# nRF24L01-Module.net
KiCad netlist of a schematic drawn in Altium Designer
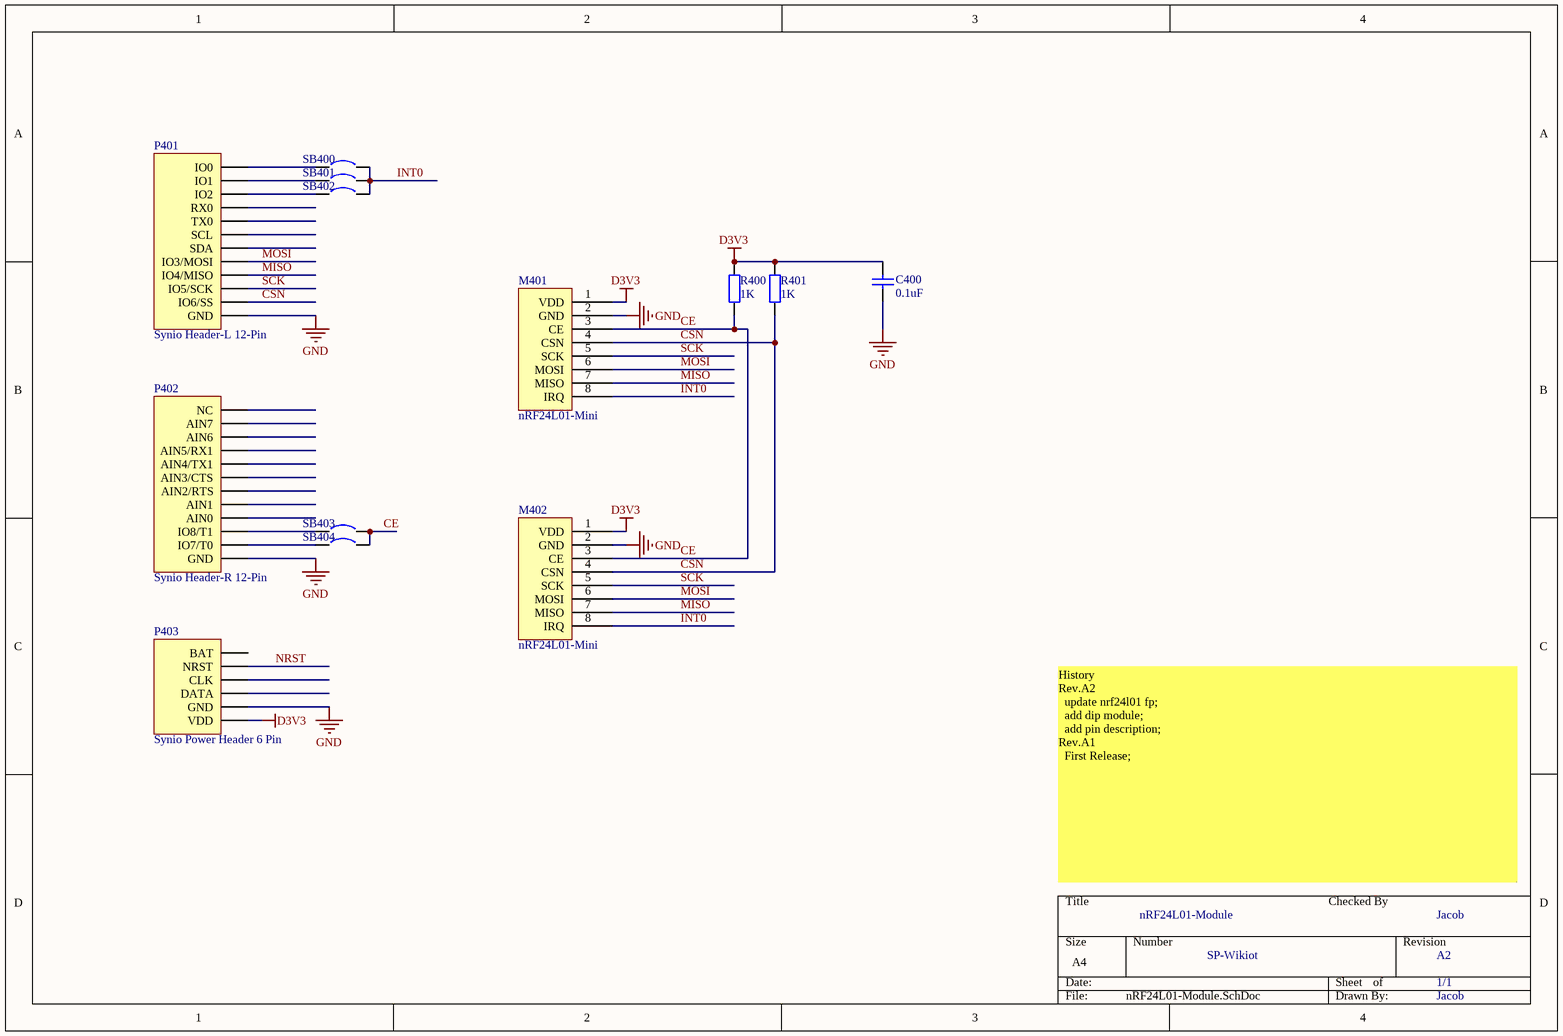
[diagram p0: nRF24L01-Module.SchDoc]

(export (version "E")
  (design (tool "Eeschema 10.0.6"))
  (components
    (comp (ref "C400")
      (value "0.1uF")
      (footprint "C0603L")
      (description "Capacitor")
      (libsource (lib "Misc") (part "Cap"))
    )
    (comp (ref "M401")
      (value "nRF24L01-Mini")
      (footprint "nRF24L01-Mini-All")
      (libsource (lib "Module") (part "nRF24L01-Mini"))
    )
    (comp (ref "M402")
      (value "nRF24L01-Mini")
      (footprint "nRF24L01-DIP")
      (libsource (lib "Module") (part "nRF24L01-Mini"))
    )
    (comp (ref "P401")
      (value "Synio Header-L 12-Pin")
      (footprint "HDR1X12")
      (description "Synio Header-L, 12-Pin")
      (fields (field (name "PUBLISHER") "Altium Limited"))
      (libsource (lib "Connector") (part "Synio Header-L 12-Pin"))
    )
    (comp (ref "P402")
      (value "Synio Header-R 12-Pin")
      (footprint "HDR1X12")
      (description "Synio Header-R, 12-Pin")
      (fields (field (name "PUBLISHER") "Altium Limited"))
      (libsource (lib "Connector") (part "Synio Header-R 12-Pin"))
    )
    (comp (ref "P403")
      (value "Synio Power Header 6 Pin")
      (footprint "HDR1X6/2.54MM")
      (libsource (lib "Connector") (part "Synio Power Header 6 Pin"))
    )
    (comp (ref "R400")
      (value "1K")
      (footprint "R0603")
      (description "Resistor")
      (fields (field (name "PUBLISHER") "Altium Limited"))
      (libsource (lib "Misc") (part "Res"))
    )
    (comp (ref "R401")
      (value "1K")
      (footprint "R0603")
      (description "Resistor")
      (fields (field (name "PUBLISHER") "Altium Limited"))
      (libsource (lib "Misc") (part "Res"))
    )
    (comp (ref "SB400")
      (value "Circuit Breaker")
      (footprint "JP2_SMD")
      (fields (field (name "PUBLISHER") "Altium Limited"))
      (libsource (lib "Misc") (part "Circuit Breaker"))
    )
    (comp (ref "SB401")
      (value "Circuit Breaker")
      (footprint "JP2_SMD")
      (fields (field (name "PUBLISHER") "Altium Limited"))
      (libsource (lib "Misc") (part "Circuit Breaker"))
    )
    (comp (ref "SB402")
      (value "Circuit Breaker")
      (footprint "JP2_SMD")
      (fields (field (name "PUBLISHER") "Altium Limited"))
      (libsource (lib "Misc") (part "Circuit Breaker"))
    )
    (comp (ref "SB403")
      (value "Circuit Breaker")
      (footprint "JP2_SMD")
      (fields (field (name "PUBLISHER") "Altium Limited"))
      (libsource (lib "Misc") (part "Circuit Breaker"))
    )
    (comp (ref "SB404")
      (value "Circuit Breaker")
      (footprint "JP2_SMD")
      (fields (field (name "PUBLISHER") "Altium Limited"))
      (libsource (lib "Misc") (part "Circuit Breaker"))
    )
  )
  (nets
    (net (code "1") (name "/CE") (class "Default")
      (node (ref "M401") (pin "3") (pinfunction "CE_3") (pintype "passive"))
      (node (ref "M402") (pin "3") (pinfunction "CE_3") (pintype "passive"))
      (node (ref "R400") (pin "2") (pinfunction "2_2") (pintype "passive"))
      (node (ref "SB403") (pin "2") (pinfunction "2_2") (pintype "passive"))
      (node (ref "SB404") (pin "2") (pinfunction "2_2") (pintype "passive"))
    )
    (net (code "2") (name "/CSN") (class "Default")
      (node (ref "M401") (pin "4") (pinfunction "CSN_4") (pintype "passive"))
      (node (ref "M402") (pin "4") (pinfunction "CSN_4") (pintype "passive"))
      (node (ref "P401") (pin "2") (pinfunction "IO6/SS_2") (pintype "passive"))
      (node (ref "R401") (pin "2") (pinfunction "2_2") (pintype "passive"))
    )
    (net (code "3") (name "/INT0") (class "Default")
      (node (ref "M401") (pin "8") (pinfunction "IRQ_8") (pintype "passive"))
      (node (ref "M402") (pin "8") (pinfunction "IRQ_8") (pintype "passive"))
      (node (ref "SB400") (pin "2") (pinfunction "2_2") (pintype "passive"))
      (node (ref "SB401") (pin "2") (pinfunction "2_2") (pintype "passive"))
      (node (ref "SB402") (pin "2") (pinfunction "2_2") (pintype "passive"))
    )
    (net (code "4") (name "/MISO") (class "Default")
      (node (ref "M401") (pin "7") (pinfunction "MISO_7") (pintype "passive"))
      (node (ref "M402") (pin "7") (pinfunction "MISO_7") (pintype "passive"))
      (node (ref "P401") (pin "4") (pinfunction "IO4/MISO_4") (pintype "passive"))
    )
    (net (code "5") (name "/MOSI") (class "Default")
      (node (ref "M401") (pin "6") (pinfunction "MOSI_6") (pintype "passive"))
      (node (ref "M402") (pin "6") (pinfunction "MOSI_6") (pintype "passive"))
      (node (ref "P401") (pin "5") (pinfunction "IO3/MOSI_5") (pintype "passive"))
    )
    (net (code "6") (name "/NRST") (class "Default")
      (node (ref "P403") (pin "5") (pinfunction "NRST_5") (pintype "passive"))
    )
    (net (code "7") (name "/SCK") (class "Default")
      (node (ref "M401") (pin "5") (pinfunction "SCK_5") (pintype "passive"))
      (node (ref "M402") (pin "5") (pinfunction "SCK_5") (pintype "passive"))
      (node (ref "P401") (pin "3") (pinfunction "IO5/SCK_3") (pintype "passive"))
    )
    (net (code "8") (name "D3V3") (class "Default")
      (node (ref "C400") (pin "1") (pinfunction "1_1") (pintype "passive"))
      (node (ref "M401") (pin "1") (pinfunction "VDD_1") (pintype "passive"))
      (node (ref "M402") (pin "1") (pinfunction "VDD_1") (pintype "passive"))
      (node (ref "P403") (pin "1") (pinfunction "VDD_1") (pintype "passive"))
      (node (ref "R400") (pin "1") (pinfunction "1_1") (pintype "passive"))
      (node (ref "R401") (pin "1") (pinfunction "1_1") (pintype "passive"))
    )
    (net (code "9") (name "GND") (class "Default")
      (node (ref "C400") (pin "2") (pinfunction "2_2") (pintype "passive"))
      (node (ref "M401") (pin "2") (pinfunction "GND_2") (pintype "passive"))
      (node (ref "M402") (pin "2") (pinfunction "GND_2") (pintype "passive"))
      (node (ref "P401") (pin "1") (pinfunction "GND_1") (pintype "passive"))
      (node (ref "P402") (pin "1") (pinfunction "GND_1") (pintype "passive"))
      (node (ref "P403") (pin "2") (pinfunction "GND_2") (pintype "passive"))
    )
    (net (code "10") (name "Net-(P401-IO0)") (class "Default")
      (node (ref "P401") (pin "12") (pinfunction "IO0_12") (pintype "passive"))
      (node (ref "SB400") (pin "1") (pinfunction "1_1") (pintype "passive"))
    )
    (net (code "11") (name "Net-(P401-IO1)") (class "Default")
      (node (ref "P401") (pin "11") (pinfunction "IO1_11") (pintype "passive"))
      (node (ref "SB401") (pin "1") (pinfunction "1_1") (pintype "passive"))
    )
    (net (code "12") (name "Net-(P401-IO2)") (class "Default")
      (node (ref "P401") (pin "10") (pinfunction "IO2_10") (pintype "passive"))
      (node (ref "SB402") (pin "1") (pinfunction "1_1") (pintype "passive"))
    )
    (net (code "13") (name "Net-(P402-IO7{slash}T0)") (class "Default")
      (node (ref "P402") (pin "2") (pinfunction "IO7/T0_2") (pintype "passive"))
      (node (ref "SB404") (pin "1") (pinfunction "1_1") (pintype "passive"))
    )
    (net (code "14") (name "Net-(P402-IO8{slash}T1)") (class "Default")
      (node (ref "P402") (pin "3") (pinfunction "IO8/T1_3") (pintype "passive"))
      (node (ref "SB403") (pin "1") (pinfunction "1_1") (pintype "passive"))
    )
    (net (code "15") (name "unconnected-(P401-RX0-Pad9)") (class "Default")
      (node (ref "P401") (pin "9") (pinfunction "RX0_9") (pintype "passive"))
    )
    (net (code "16") (name "unconnected-(P401-SCL-Pad7)") (class "Default")
      (node (ref "P401") (pin "7") (pinfunction "SCL_7") (pintype "passive"))
    )
    (net (code "17") (name "unconnected-(P401-SDA-Pad6)") (class "Default")
      (node (ref "P401") (pin "6") (pinfunction "SDA_6") (pintype "passive"))
    )
    (net (code "18") (name "unconnected-(P401-TX0-Pad8)") (class "Default")
      (node (ref "P401") (pin "8") (pinfunction "TX0_8") (pintype "passive"))
    )
    (net (code "19") (name "unconnected-(P402-AIN0-Pad4)") (class "Default")
      (node (ref "P402") (pin "4") (pinfunction "AIN0_4") (pintype "passive"))
    )
    (net (code "20") (name "unconnected-(P402-AIN1-Pad5)") (class "Default")
      (node (ref "P402") (pin "5") (pinfunction "AIN1_5") (pintype "passive"))
    )
    (net (code "21") (name "unconnected-(P402-AIN2{slash}RTS-Pad6)") (class "Default")
      (node (ref "P402") (pin "6") (pinfunction "AIN2/RTS_6") (pintype "passive"))
    )
    (net (code "22") (name "unconnected-(P402-AIN3{slash}CTS-Pad7)") (class "Default")
      (node (ref "P402") (pin "7") (pinfunction "AIN3/CTS_7") (pintype "passive"))
    )
    (net (code "23") (name "unconnected-(P402-AIN4{slash}TX1-Pad8)") (class "Default")
      (node (ref "P402") (pin "8") (pinfunction "AIN4/TX1_8") (pintype "passive"))
    )
    (net (code "24") (name "unconnected-(P402-AIN5{slash}RX1-Pad9)") (class "Default")
      (node (ref "P402") (pin "9") (pinfunction "AIN5/RX1_9") (pintype "passive"))
    )
    (net (code "25") (name "unconnected-(P402-AIN6-Pad10)") (class "Default")
      (node (ref "P402") (pin "10") (pinfunction "AIN6_10") (pintype "passive"))
    )
    (net (code "26") (name "unconnected-(P402-AIN7-Pad11)") (class "Default")
      (node (ref "P402") (pin "11") (pinfunction "AIN7_11") (pintype "passive"))
    )
    (net (code "27") (name "unconnected-(P402-NC-Pad12)") (class "Default")
      (node (ref "P402") (pin "12") (pinfunction "NC_12") (pintype "passive"))
    )
    (net (code "28") (name "unconnected-(P403-BAT-Pad6)") (class "Default")
      (node (ref "P403") (pin "6") (pinfunction "BAT_6") (pintype "passive"))
    )
    (net (code "29") (name "unconnected-(P403-CLK-Pad4)") (class "Default")
      (node (ref "P403") (pin "4") (pinfunction "CLK_4") (pintype "passive"))
    )
    (net (code "30") (name "unconnected-(P403-DATA-Pad3)") (class "Default")
      (node (ref "P403") (pin "3") (pinfunction "DATA_3") (pintype "passive"))
    )
  )
)
